# Breakout.net
KiCad netlist of a schematic drawn in EAGLE
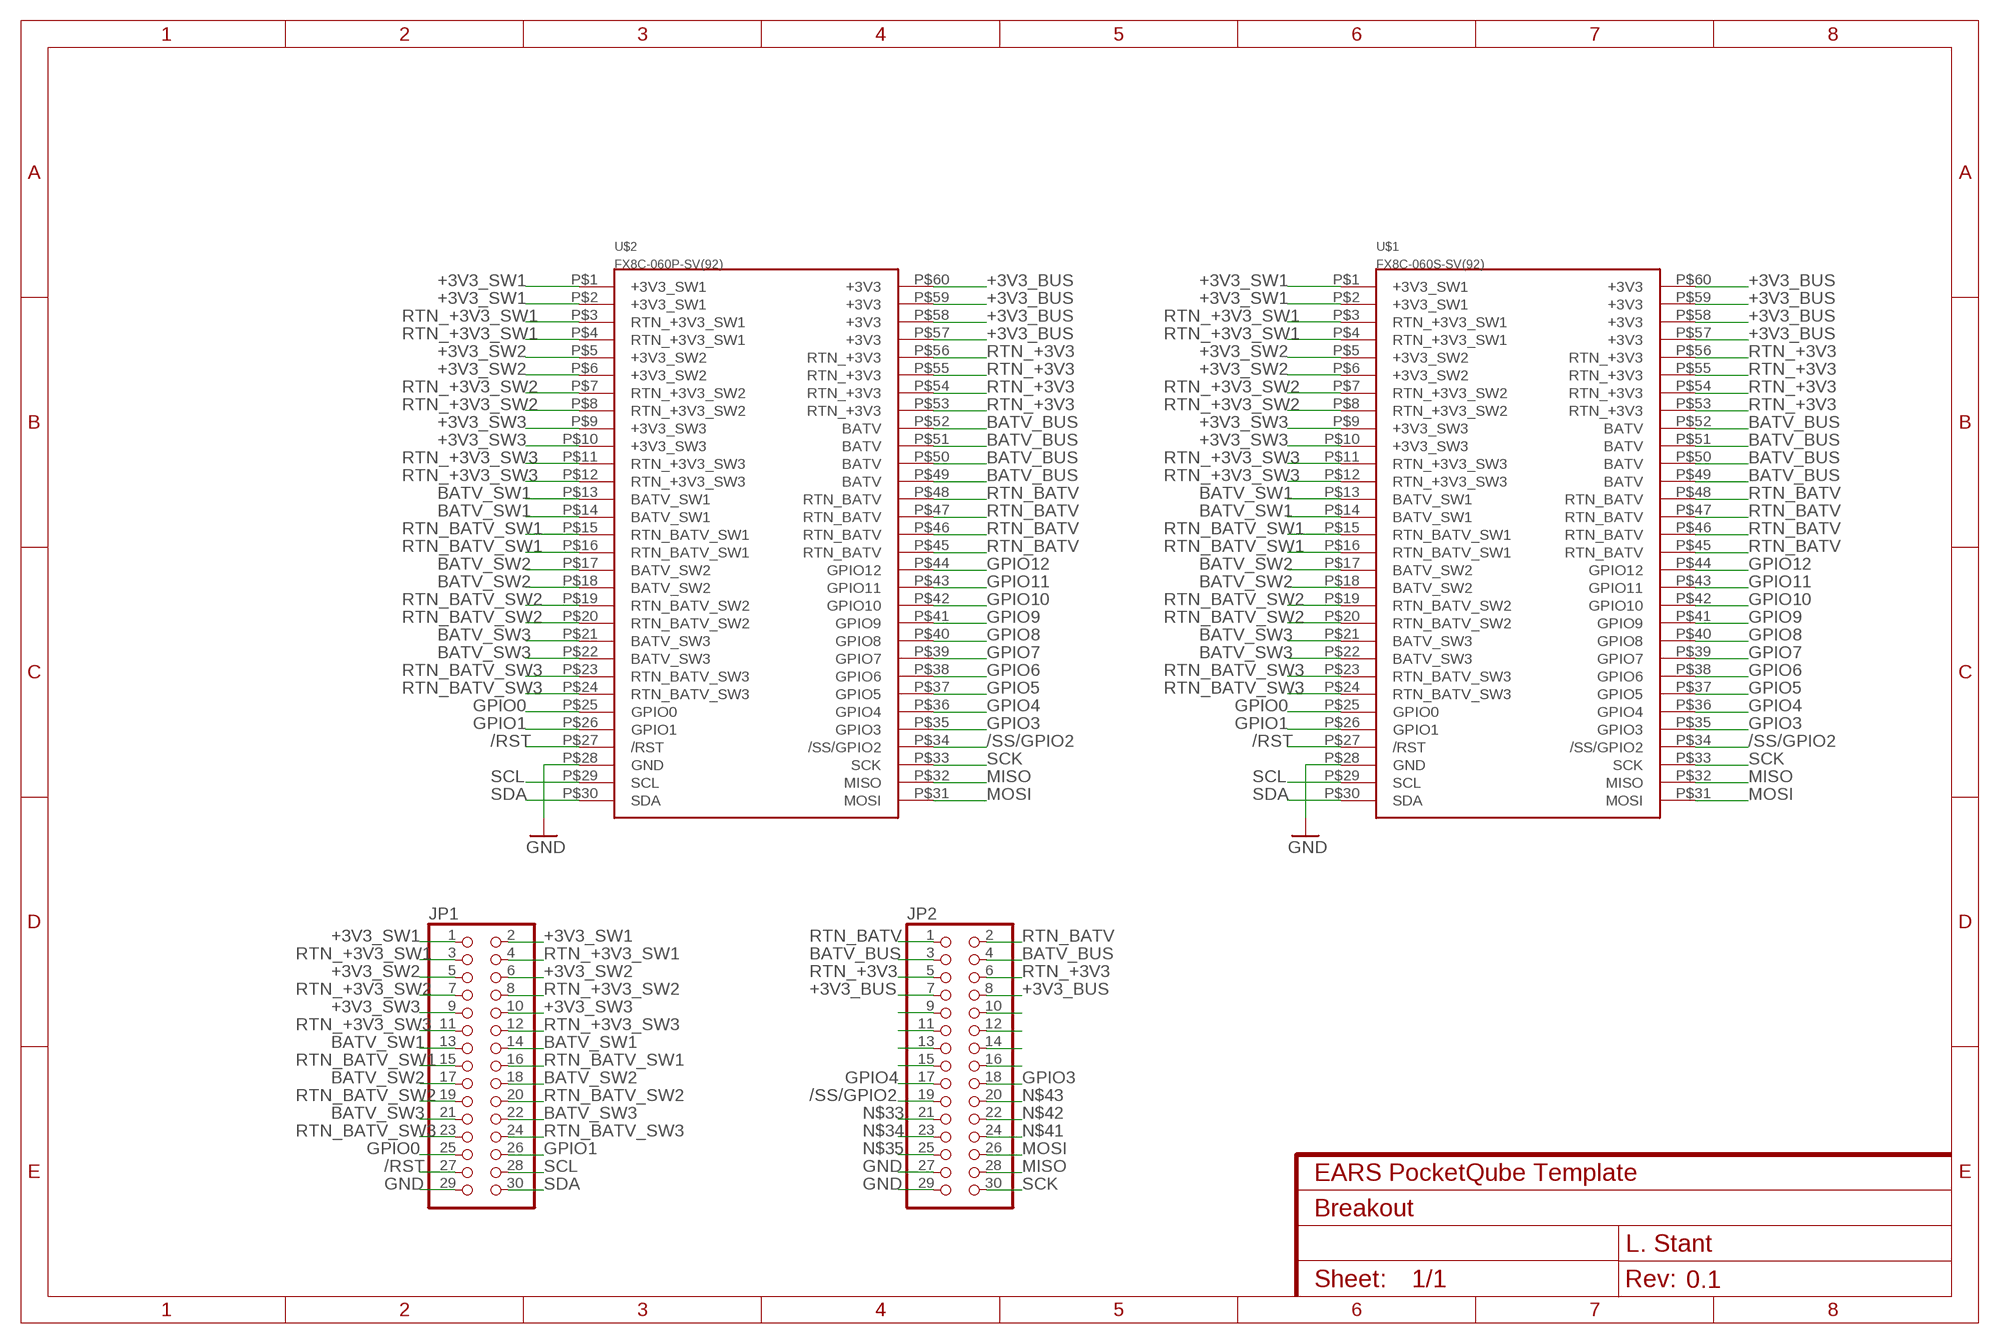
[diagram p0: schematic, sheet 1]

(export (version "E")
  (design (tool "Eeschema 10.0.6"))
  (components
    (comp (ref "JP1")
      (value "PINHD-2X15")
      (footprint "eagle-import:2X15")
      (libsource (lib "eagle-import") (part "PINHD-2X15"))
    )
    (comp (ref "JP2")
      (value "PINHD-2X15")
      (footprint "eagle-import:2X15")
      (libsource (lib "eagle-import") (part "PINHD-2X15"))
    )
    (comp (ref "U$1")
      (value "FX8C-060S-SV(92)")
      (footprint "eagle-import:FX8C-060S-SV(92)")
      (libsource (lib "eagle-import") (part "FX8C-060S-SV(92)"))
    )
    (comp (ref "U$2")
      (value "FX8C-060P-SV(92)")
      (footprint "eagle-import:FX8C-060P-SV(92)")
      (libsource (lib "eagle-import") (part "FX8C-060P-SV(92)"))
    )
  )
  (nets
    (net (code "1") (name "/+3V3_BUS") (class "Default")
      (node (ref "JP2") (pin "7") (pinfunction "7_7") (pintype "passive"))
      (node (ref "JP2") (pin "8") (pinfunction "8_8") (pintype "passive"))
      (node (ref "U$1") (pin "P$57") (pinfunction "+3V3_P$57") (pintype "power_in"))
      (node (ref "U$1") (pin "P$58") (pinfunction "+3V3_P$58") (pintype "power_in"))
      (node (ref "U$1") (pin "P$59") (pinfunction "+3V3_P$59") (pintype "power_in"))
      (node (ref "U$1") (pin "P$60") (pinfunction "+3V3_P$60") (pintype "power_in"))
      (node (ref "U$2") (pin "P$57") (pinfunction "+3V3_P$57") (pintype "power_in"))
      (node (ref "U$2") (pin "P$58") (pinfunction "+3V3_P$58") (pintype "power_in"))
      (node (ref "U$2") (pin "P$59") (pinfunction "+3V3_P$59") (pintype "power_in"))
      (node (ref "U$2") (pin "P$60") (pinfunction "+3V3_P$60") (pintype "power_in"))
    )
    (net (code "2") (name "/+3V3_SW1") (class "Default")
      (node (ref "JP1") (pin "1") (pinfunction "1_1") (pintype "passive"))
      (node (ref "JP1") (pin "2") (pinfunction "2_2") (pintype "passive"))
      (node (ref "U$1") (pin "P$1") (pinfunction "+3V3_SW1_P$1") (pintype "power_in"))
      (node (ref "U$1") (pin "P$2") (pinfunction "+3V3_SW1_P$2") (pintype "power_in"))
      (node (ref "U$2") (pin "P$1") (pinfunction "+3V3_SW1_P$1") (pintype "power_in"))
      (node (ref "U$2") (pin "P$2") (pinfunction "+3V3_SW1_P$2") (pintype "power_in"))
    )
    (net (code "3") (name "/+3V3_SW2") (class "Default")
      (node (ref "JP1") (pin "5") (pinfunction "5_5") (pintype "passive"))
      (node (ref "JP1") (pin "6") (pinfunction "6_6") (pintype "passive"))
      (node (ref "U$1") (pin "P$5") (pinfunction "+3V3_SW2_P$5") (pintype "power_in"))
      (node (ref "U$1") (pin "P$6") (pinfunction "+3V3_SW2_P$6") (pintype "power_in"))
      (node (ref "U$2") (pin "P$5") (pinfunction "+3V3_SW2_P$5") (pintype "power_in"))
      (node (ref "U$2") (pin "P$6") (pinfunction "+3V3_SW2_P$6") (pintype "power_in"))
    )
    (net (code "4") (name "/+3V3_SW3") (class "Default")
      (node (ref "JP1") (pin "10") (pinfunction "10_10") (pintype "passive"))
      (node (ref "JP1") (pin "9") (pinfunction "9_9") (pintype "passive"))
      (node (ref "U$1") (pin "P$10") (pinfunction "+3V3_SW3_P$10") (pintype "power_in"))
      (node (ref "U$1") (pin "P$9") (pinfunction "+3V3_SW3_P$9") (pintype "power_in"))
      (node (ref "U$2") (pin "P$10") (pinfunction "+3V3_SW3_P$10") (pintype "power_in"))
      (node (ref "U$2") (pin "P$9") (pinfunction "+3V3_SW3_P$9") (pintype "power_in"))
    )
    (net (code "5") (name "/BATV_BUS") (class "Default")
      (node (ref "JP2") (pin "3") (pinfunction "3_3") (pintype "passive"))
      (node (ref "JP2") (pin "4") (pinfunction "4_4") (pintype "passive"))
      (node (ref "U$1") (pin "P$49") (pinfunction "BATV_P$49") (pintype "power_in"))
      (node (ref "U$1") (pin "P$50") (pinfunction "BATV_P$50") (pintype "power_in"))
      (node (ref "U$1") (pin "P$51") (pinfunction "BATV_P$51") (pintype "power_in"))
      (node (ref "U$1") (pin "P$52") (pinfunction "BATV_P$52") (pintype "power_in"))
      (node (ref "U$2") (pin "P$49") (pinfunction "BATV_P$49") (pintype "power_in"))
      (node (ref "U$2") (pin "P$50") (pinfunction "BATV_P$50") (pintype "power_in"))
      (node (ref "U$2") (pin "P$51") (pinfunction "BATV_P$51") (pintype "power_in"))
      (node (ref "U$2") (pin "P$52") (pinfunction "BATV_P$52") (pintype "power_in"))
    )
    (net (code "6") (name "/BATV_SW1") (class "Default")
      (node (ref "JP1") (pin "13") (pinfunction "13_13") (pintype "passive"))
      (node (ref "JP1") (pin "14") (pinfunction "14_14") (pintype "passive"))
      (node (ref "U$1") (pin "P$13") (pinfunction "BATV_SW1_P$13") (pintype "power_in"))
      (node (ref "U$1") (pin "P$14") (pinfunction "BATV_SW1_P$14") (pintype "power_in"))
      (node (ref "U$2") (pin "P$13") (pinfunction "BATV_SW1_P$13") (pintype "power_in"))
      (node (ref "U$2") (pin "P$14") (pinfunction "BATV_SW1_P$14") (pintype "power_in"))
    )
    (net (code "7") (name "/BATV_SW2") (class "Default")
      (node (ref "JP1") (pin "17") (pinfunction "17_17") (pintype "passive"))
      (node (ref "JP1") (pin "18") (pinfunction "18_18") (pintype "passive"))
      (node (ref "U$1") (pin "P$17") (pinfunction "BATV_SW2_P$17") (pintype "power_in"))
      (node (ref "U$1") (pin "P$18") (pinfunction "BATV_SW2_P$18") (pintype "power_in"))
      (node (ref "U$2") (pin "P$17") (pinfunction "BATV_SW2_P$17") (pintype "power_in"))
      (node (ref "U$2") (pin "P$18") (pinfunction "BATV_SW2_P$18") (pintype "power_in"))
    )
    (net (code "8") (name "/BATV_SW3") (class "Default")
      (node (ref "JP1") (pin "21") (pinfunction "21_21") (pintype "passive"))
      (node (ref "JP1") (pin "22") (pinfunction "22_22") (pintype "passive"))
      (node (ref "U$1") (pin "P$21") (pinfunction "BATV_SW3_P$21") (pintype "power_in"))
      (node (ref "U$1") (pin "P$22") (pinfunction "BATV_SW3_P$22") (pintype "power_in"))
      (node (ref "U$2") (pin "P$21") (pinfunction "BATV_SW3_P$21") (pintype "power_in"))
      (node (ref "U$2") (pin "P$22") (pinfunction "BATV_SW3_P$22") (pintype "power_in"))
    )
    (net (code "9") (name "/GPIO0") (class "Default")
      (node (ref "JP1") (pin "25") (pinfunction "25_25") (pintype "passive"))
      (node (ref "U$1") (pin "P$25") (pinfunction "GPIO0_P$25") (pintype "bidirectional"))
      (node (ref "U$2") (pin "P$25") (pinfunction "GPIO0_P$25") (pintype "bidirectional"))
    )
    (net (code "10") (name "/GPIO1") (class "Default")
      (node (ref "JP1") (pin "26") (pinfunction "26_26") (pintype "passive"))
      (node (ref "U$1") (pin "P$26") (pinfunction "GPIO1_P$26") (pintype "bidirectional"))
      (node (ref "U$2") (pin "P$26") (pinfunction "GPIO1_P$26") (pintype "bidirectional"))
    )
    (net (code "11") (name "/GPIO3") (class "Default")
      (node (ref "JP2") (pin "18") (pinfunction "18_18") (pintype "passive"))
      (node (ref "U$1") (pin "P$35") (pinfunction "GPIO3_P$35") (pintype "bidirectional"))
      (node (ref "U$2") (pin "P$35") (pinfunction "GPIO3_P$35") (pintype "bidirectional"))
    )
    (net (code "12") (name "/GPIO4") (class "Default")
      (node (ref "JP2") (pin "17") (pinfunction "17_17") (pintype "passive"))
      (node (ref "U$1") (pin "P$36") (pinfunction "GPIO4_P$36") (pintype "bidirectional"))
      (node (ref "U$2") (pin "P$36") (pinfunction "GPIO4_P$36") (pintype "bidirectional"))
    )
    (net (code "13") (name "/GPIO5") (class "Default")
      (node (ref "JP2") (pin "16") (pinfunction "16_16") (pintype "passive"))
      (node (ref "U$1") (pin "P$37") (pinfunction "GPIO5_P$37") (pintype "bidirectional"))
      (node (ref "U$2") (pin "P$37") (pinfunction "GPIO5_P$37") (pintype "bidirectional"))
    )
    (net (code "14") (name "/GPIO6") (class "Default")
      (node (ref "JP2") (pin "15") (pinfunction "15_15") (pintype "passive"))
      (node (ref "U$1") (pin "P$38") (pinfunction "GPIO6_P$38") (pintype "bidirectional"))
      (node (ref "U$2") (pin "P$38") (pinfunction "GPIO6_P$38") (pintype "bidirectional"))
    )
    (net (code "15") (name "/GPIO7") (class "Default")
      (node (ref "JP2") (pin "14") (pinfunction "14_14") (pintype "passive"))
      (node (ref "U$1") (pin "P$39") (pinfunction "GPIO7_P$39") (pintype "bidirectional"))
      (node (ref "U$2") (pin "P$39") (pinfunction "GPIO7_P$39") (pintype "bidirectional"))
    )
    (net (code "16") (name "/GPIO8") (class "Default")
      (node (ref "JP2") (pin "13") (pinfunction "13_13") (pintype "passive"))
      (node (ref "U$1") (pin "P$40") (pinfunction "GPIO8_P$40") (pintype "bidirectional"))
      (node (ref "U$2") (pin "P$40") (pinfunction "GPIO8_P$40") (pintype "bidirectional"))
    )
    (net (code "17") (name "/GPIO9") (class "Default")
      (node (ref "JP2") (pin "12") (pinfunction "12_12") (pintype "passive"))
      (node (ref "U$1") (pin "P$41") (pinfunction "GPIO9_P$41") (pintype "bidirectional"))
      (node (ref "U$2") (pin "P$41") (pinfunction "GPIO9_P$41") (pintype "bidirectional"))
    )
    (net (code "18") (name "/GPIO10") (class "Default")
      (node (ref "JP2") (pin "11") (pinfunction "11_11") (pintype "passive"))
      (node (ref "U$1") (pin "P$42") (pinfunction "GPIO10_P$42") (pintype "bidirectional"))
      (node (ref "U$2") (pin "P$42") (pinfunction "GPIO10_P$42") (pintype "bidirectional"))
    )
    (net (code "19") (name "/GPIO11") (class "Default")
      (node (ref "JP2") (pin "10") (pinfunction "10_10") (pintype "passive"))
      (node (ref "U$1") (pin "P$43") (pinfunction "GPIO11_P$43") (pintype "bidirectional"))
      (node (ref "U$2") (pin "P$43") (pinfunction "GPIO11_P$43") (pintype "bidirectional"))
    )
    (net (code "20") (name "/GPIO12") (class "Default")
      (node (ref "JP2") (pin "9") (pinfunction "9_9") (pintype "passive"))
      (node (ref "U$1") (pin "P$44") (pinfunction "GPIO12_P$44") (pintype "bidirectional"))
      (node (ref "U$2") (pin "P$44") (pinfunction "GPIO12_P$44") (pintype "bidirectional"))
    )
    (net (code "21") (name "/MISO") (class "Default")
      (node (ref "JP2") (pin "28") (pinfunction "28_28") (pintype "passive"))
      (node (ref "U$1") (pin "P$32") (pinfunction "MISO_P$32") (pintype "bidirectional"))
      (node (ref "U$2") (pin "P$32") (pinfunction "MISO_P$32") (pintype "bidirectional"))
    )
    (net (code "22") (name "/MOSI") (class "Default")
      (node (ref "JP2") (pin "26") (pinfunction "26_26") (pintype "passive"))
      (node (ref "U$1") (pin "P$31") (pinfunction "MOSI_P$31") (pintype "bidirectional"))
      (node (ref "U$2") (pin "P$31") (pinfunction "MOSI_P$31") (pintype "bidirectional"))
    )
    (net (code "23") (name "/N$33") (class "Default")
      (node (ref "JP2") (pin "21") (pinfunction "21_21") (pintype "passive"))
    )
    (net (code "24") (name "/N$34") (class "Default")
      (node (ref "JP2") (pin "23") (pinfunction "23_23") (pintype "passive"))
    )
    (net (code "25") (name "/N$35") (class "Default")
      (node (ref "JP2") (pin "25") (pinfunction "25_25") (pintype "passive"))
    )
    (net (code "26") (name "/N$41") (class "Default")
      (node (ref "JP2") (pin "24") (pinfunction "24_24") (pintype "passive"))
    )
    (net (code "27") (name "/N$42") (class "Default")
      (node (ref "JP2") (pin "22") (pinfunction "22_22") (pintype "passive"))
    )
    (net (code "28") (name "/N$43") (class "Default")
      (node (ref "JP2") (pin "20") (pinfunction "20_20") (pintype "passive"))
    )
    (net (code "29") (name "/RTN_+3V3") (class "Default")
      (node (ref "JP2") (pin "5") (pinfunction "5_5") (pintype "passive"))
      (node (ref "JP2") (pin "6") (pinfunction "6_6") (pintype "passive"))
      (node (ref "U$1") (pin "P$53") (pinfunction "RTN_+3V3_P$53") (pintype "power_in"))
      (node (ref "U$1") (pin "P$54") (pinfunction "RTN_+3V3_P$54") (pintype "power_in"))
      (node (ref "U$1") (pin "P$55") (pinfunction "RTN_+3V3_P$55") (pintype "power_in"))
      (node (ref "U$1") (pin "P$56") (pinfunction "RTN_+3V3_P$56") (pintype "power_in"))
      (node (ref "U$2") (pin "P$53") (pinfunction "RTN_+3V3_P$53") (pintype "power_in"))
      (node (ref "U$2") (pin "P$54") (pinfunction "RTN_+3V3_P$54") (pintype "power_in"))
      (node (ref "U$2") (pin "P$55") (pinfunction "RTN_+3V3_P$55") (pintype "power_in"))
      (node (ref "U$2") (pin "P$56") (pinfunction "RTN_+3V3_P$56") (pintype "power_in"))
    )
    (net (code "30") (name "/RTN_+3V3_SW1") (class "Default")
      (node (ref "JP1") (pin "3") (pinfunction "3_3") (pintype "passive"))
      (node (ref "JP1") (pin "4") (pinfunction "4_4") (pintype "passive"))
      (node (ref "U$1") (pin "P$3") (pinfunction "RTN_+3V3_SW1_P$3") (pintype "power_in"))
      (node (ref "U$1") (pin "P$4") (pinfunction "RTN_+3V3_SW1_P$4") (pintype "power_in"))
      (node (ref "U$2") (pin "P$3") (pinfunction "RTN_+3V3_SW1_P$3") (pintype "power_in"))
      (node (ref "U$2") (pin "P$4") (pinfunction "RTN_+3V3_SW1_P$4") (pintype "power_in"))
    )
    (net (code "31") (name "/RTN_+3V3_SW2") (class "Default")
      (node (ref "JP1") (pin "7") (pinfunction "7_7") (pintype "passive"))
      (node (ref "JP1") (pin "8") (pinfunction "8_8") (pintype "passive"))
      (node (ref "U$1") (pin "P$7") (pinfunction "RTN_+3V3_SW2_P$7") (pintype "power_in"))
      (node (ref "U$1") (pin "P$8") (pinfunction "RTN_+3V3_SW2_P$8") (pintype "power_in"))
      (node (ref "U$2") (pin "P$7") (pinfunction "RTN_+3V3_SW2_P$7") (pintype "power_in"))
      (node (ref "U$2") (pin "P$8") (pinfunction "RTN_+3V3_SW2_P$8") (pintype "power_in"))
    )
    (net (code "32") (name "/RTN_+3V3_SW3") (class "Default")
      (node (ref "JP1") (pin "11") (pinfunction "11_11") (pintype "passive"))
      (node (ref "JP1") (pin "12") (pinfunction "12_12") (pintype "passive"))
      (node (ref "U$1") (pin "P$11") (pinfunction "RTN_+3V3_SW3_P$11") (pintype "power_in"))
      (node (ref "U$1") (pin "P$12") (pinfunction "RTN_+3V3_SW3_P$12") (pintype "power_in"))
      (node (ref "U$2") (pin "P$11") (pinfunction "RTN_+3V3_SW3_P$11") (pintype "power_in"))
      (node (ref "U$2") (pin "P$12") (pinfunction "RTN_+3V3_SW3_P$12") (pintype "power_in"))
    )
    (net (code "33") (name "/RTN_BATV") (class "Default")
      (node (ref "JP2") (pin "1") (pinfunction "1_1") (pintype "passive"))
      (node (ref "JP2") (pin "2") (pinfunction "2_2") (pintype "passive"))
      (node (ref "U$1") (pin "P$45") (pinfunction "RTN_BATV_P$45") (pintype "power_in"))
      (node (ref "U$1") (pin "P$46") (pinfunction "RTN_BATV_P$46") (pintype "power_in"))
      (node (ref "U$1") (pin "P$47") (pinfunction "RTN_BATV_P$47") (pintype "power_in"))
      (node (ref "U$1") (pin "P$48") (pinfunction "RTN_BATV_P$48") (pintype "power_in"))
      (node (ref "U$2") (pin "P$45") (pinfunction "RTN_BATV_P$45") (pintype "power_in"))
      (node (ref "U$2") (pin "P$46") (pinfunction "RTN_BATV_P$46") (pintype "power_in"))
      (node (ref "U$2") (pin "P$47") (pinfunction "RTN_BATV_P$47") (pintype "power_in"))
      (node (ref "U$2") (pin "P$48") (pinfunction "RTN_BATV_P$48") (pintype "power_in"))
    )
    (net (code "34") (name "/RTN_BATV_SW1") (class "Default")
      (node (ref "JP1") (pin "15") (pinfunction "15_15") (pintype "passive"))
      (node (ref "JP1") (pin "16") (pinfunction "16_16") (pintype "passive"))
      (node (ref "U$1") (pin "P$15") (pinfunction "RTN_BATV_SW1_P$15") (pintype "power_in"))
      (node (ref "U$1") (pin "P$16") (pinfunction "RTN_BATV_SW1_P$16") (pintype "power_in"))
      (node (ref "U$2") (pin "P$15") (pinfunction "RTN_BATV_SW1_P$15") (pintype "power_in"))
      (node (ref "U$2") (pin "P$16") (pinfunction "RTN_BATV_SW1_P$16") (pintype "power_in"))
    )
    (net (code "35") (name "/RTN_BATV_SW2") (class "Default")
      (node (ref "JP1") (pin "19") (pinfunction "19_19") (pintype "passive"))
      (node (ref "JP1") (pin "20") (pinfunction "20_20") (pintype "passive"))
      (node (ref "U$1") (pin "P$19") (pinfunction "RTN_BATV_SW2_P$19") (pintype "power_in"))
      (node (ref "U$1") (pin "P$20") (pinfunction "RTN_BATV_SW2_P$20") (pintype "power_in"))
      (node (ref "U$2") (pin "P$19") (pinfunction "RTN_BATV_SW2_P$19") (pintype "power_in"))
      (node (ref "U$2") (pin "P$20") (pinfunction "RTN_BATV_SW2_P$20") (pintype "power_in"))
    )
    (net (code "36") (name "/RTN_BATV_SW3") (class "Default")
      (node (ref "JP1") (pin "23") (pinfunction "23_23") (pintype "passive"))
      (node (ref "JP1") (pin "24") (pinfunction "24_24") (pintype "passive"))
      (node (ref "U$1") (pin "P$23") (pinfunction "RTN_BATV_SW3_P$23") (pintype "power_in"))
      (node (ref "U$1") (pin "P$24") (pinfunction "RTN_BATV_SW3_P$24") (pintype "power_in"))
      (node (ref "U$2") (pin "P$23") (pinfunction "RTN_BATV_SW3_P$23") (pintype "power_in"))
      (node (ref "U$2") (pin "P$24") (pinfunction "RTN_BATV_SW3_P$24") (pintype "power_in"))
    )
    (net (code "37") (name "/SCK") (class "Default")
      (node (ref "JP2") (pin "30") (pinfunction "30_30") (pintype "passive"))
      (node (ref "U$1") (pin "P$33") (pinfunction "SCK_P$33") (pintype "bidirectional"))
      (node (ref "U$2") (pin "P$33") (pinfunction "SCK_P$33") (pintype "bidirectional"))
    )
    (net (code "38") (name "/SCL") (class "Default")
      (node (ref "JP1") (pin "28") (pinfunction "28_28") (pintype "passive"))
      (node (ref "U$1") (pin "P$29") (pinfunction "SCL_P$29") (pintype "bidirectional"))
      (node (ref "U$2") (pin "P$29") (pinfunction "SCL_P$29") (pintype "bidirectional"))
    )
    (net (code "39") (name "/SDA") (class "Default")
      (node (ref "JP1") (pin "30") (pinfunction "30_30") (pintype "passive"))
      (node (ref "U$1") (pin "P$30") (pinfunction "SDA_P$30") (pintype "bidirectional"))
      (node (ref "U$2") (pin "P$30") (pinfunction "SDA_P$30") (pintype "bidirectional"))
    )
    (net (code "40") (name "/{slash}RST") (class "Default")
      (node (ref "JP1") (pin "27") (pinfunction "27_27") (pintype "passive"))
      (node (ref "U$1") (pin "P$27") (pinfunction "/RST_P$27") (pintype "bidirectional"))
      (node (ref "U$2") (pin "P$27") (pinfunction "/RST_P$27") (pintype "bidirectional"))
    )
    (net (code "41") (name "/{slash}SS{slash}GPIO2") (class "Default")
      (node (ref "JP2") (pin "19") (pinfunction "19_19") (pintype "passive"))
      (node (ref "U$1") (pin "P$34") (pinfunction "/SS/GPIO2_P$34") (pintype "bidirectional"))
      (node (ref "U$2") (pin "P$34") (pinfunction "/SS/GPIO2_P$34") (pintype "bidirectional"))
    )
    (net (code "42") (name "GND") (class "Default")
      (node (ref "JP1") (pin "29") (pinfunction "29_29") (pintype "passive"))
      (node (ref "JP2") (pin "27") (pinfunction "27_27") (pintype "passive"))
      (node (ref "JP2") (pin "29") (pinfunction "29_29") (pintype "passive"))
      (node (ref "U$1") (pin "P$28") (pinfunction "GND_P$28") (pintype "bidirectional"))
      (node (ref "U$2") (pin "P$28") (pinfunction "GND_P$28") (pintype "bidirectional"))
    )
  )
)
